# TopLevel.net
KiCad netlist of a schematic drawn in Altium Designer
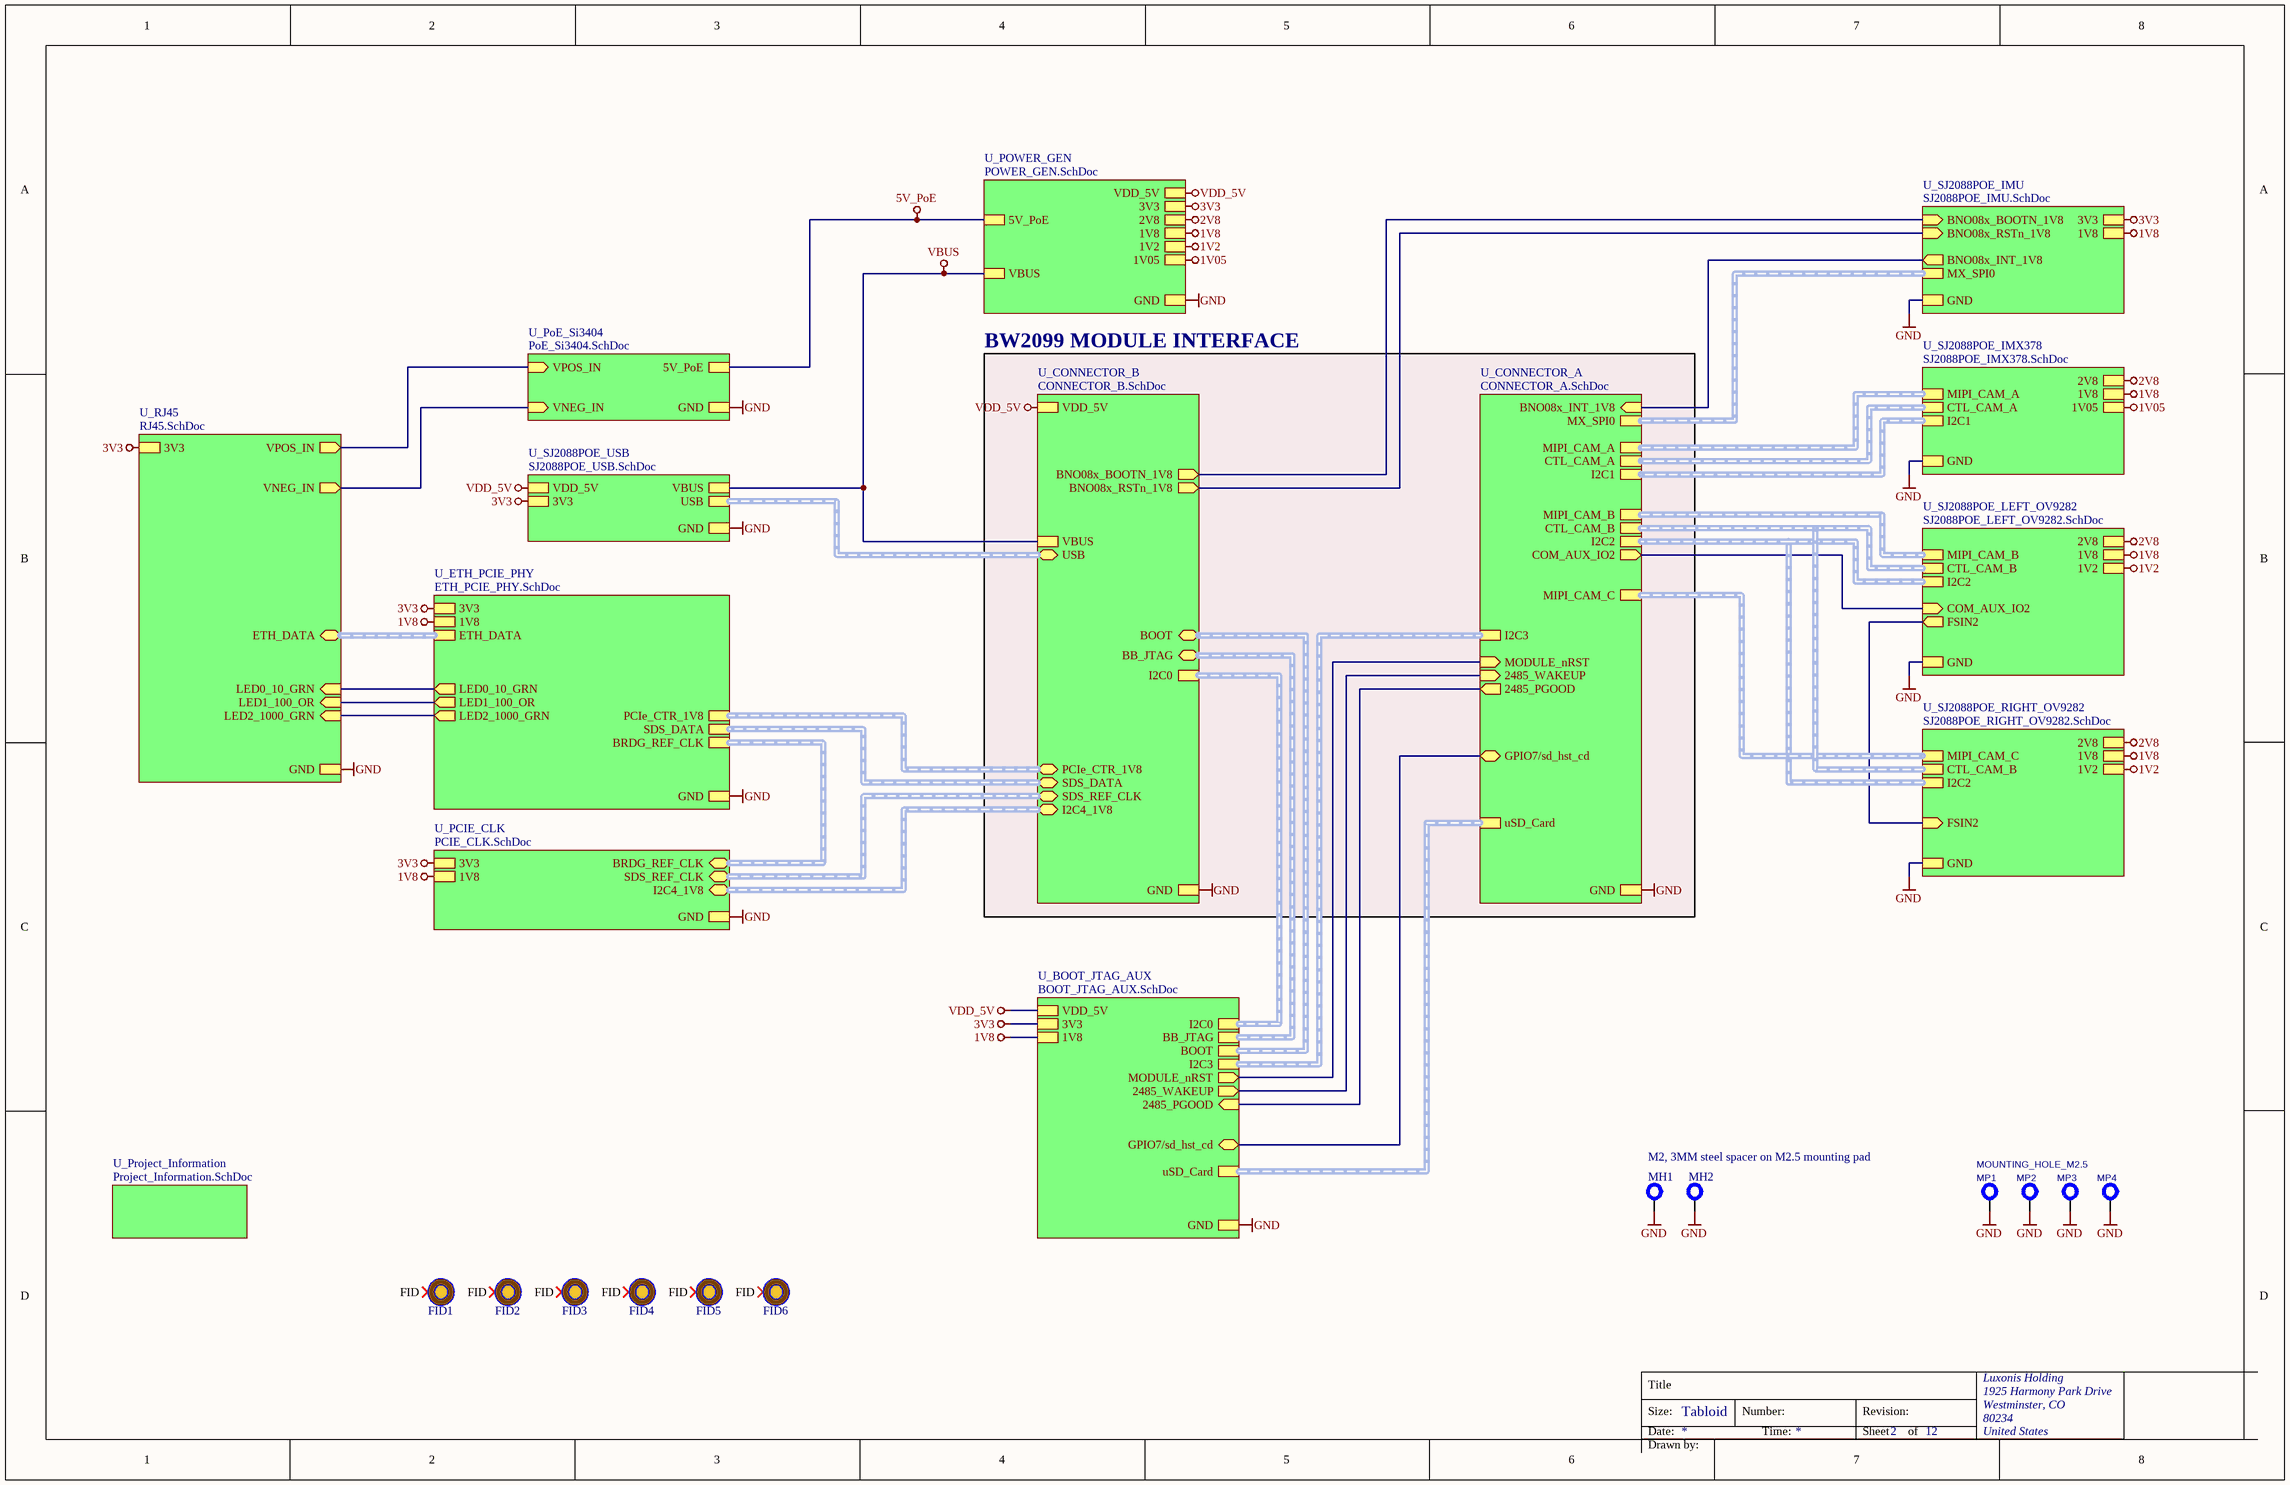
[diagram p0: TopLevel.SchDoc]

(export (version "E")
  (design (tool "Eeschema 10.0.6"))
  (components
    (comp (ref "FID1")
      (value "FIDUCIAL_ROUND_1MM")
      (footprint "LuxonisMaster:FIDUCIAL_ROUND_1MM")
      (description "Fiducial with various available footprints")
      (libsource (lib "LuxonisMaster") (part "FIDUCIAL"))
    )
    (comp (ref "FID2")
      (value "FIDUCIAL_ROUND_1MM")
      (footprint "LuxonisMaster:FIDUCIAL_ROUND_1MM")
      (description "Fiducial with various available footprints")
      (libsource (lib "LuxonisMaster") (part "FIDUCIAL"))
    )
    (comp (ref "FID3")
      (value "FIDUCIAL_ROUND_1MM")
      (footprint "LuxonisMaster:FIDUCIAL_ROUND_1MM")
      (description "Fiducial with various available footprints")
      (libsource (lib "LuxonisMaster") (part "FIDUCIAL"))
    )
    (comp (ref "FID4")
      (value "FIDUCIAL_ROUND_1MM")
      (footprint "LuxonisMaster:FIDUCIAL_ROUND_1MM")
      (description "Fiducial with various available footprints")
      (libsource (lib "LuxonisMaster") (part "FIDUCIAL"))
    )
    (comp (ref "FID5")
      (value "FIDUCIAL_ROUND_1MM")
      (footprint "LuxonisMaster:FIDUCIAL_ROUND_1MM")
      (description "Fiducial with various available footprints")
      (libsource (lib "LuxonisMaster") (part "FIDUCIAL"))
    )
    (comp (ref "FID6")
      (value "FIDUCIAL_ROUND_1MM")
      (footprint "LuxonisMaster:FIDUCIAL_ROUND_1MM")
      (description "Fiducial with various available footprints")
      (libsource (lib "LuxonisMaster") (part "FIDUCIAL"))
    )
    (comp (ref "MH1")
      (value "M2, 3MM steel spacer on M2.5 mounting pad")
      (footprint "LuxonisMaster:9774030243R")
      (description "MP ROUND STANDOFF M2X0.4 STEEL 3MM")
      (libsource (lib "LuxonisMaster") (part "9774030243R"))
    )
    (comp (ref "MH2")
      (value "M2, 3MM steel spacer on M2.5 mounting pad")
      (footprint "LuxonisMaster:9774030243R")
      (description "MP ROUND STANDOFF M2X0.4 STEEL 3MM")
      (libsource (lib "LuxonisMaster") (part "9774030243R"))
    )
    (comp (ref "MP1")
      (value "MOUNTING_HOLE_M2.5")
      (footprint "LuxonisMaster:MOUNTING_HOLE_M2.5")
      (description "=CurrentFootprint")
      (libsource (lib "LuxonisMaster") (part "MP_Mounting-Holes"))
    )
    (comp (ref "MP2")
      (value "MOUNTING_HOLE_M2.5")
      (footprint "LuxonisMaster:MOUNTING_HOLE_M2.5")
      (description "=CurrentFootprint")
      (libsource (lib "LuxonisMaster") (part "MP_Mounting-Holes"))
    )
    (comp (ref "MP3")
      (value "MOUNTING_HOLE_M2.5")
      (footprint "LuxonisMaster:MOUNTING_HOLE_M2.5")
      (description "=CurrentFootprint")
      (libsource (lib "LuxonisMaster") (part "MP_Mounting-Holes"))
    )
    (comp (ref "MP4")
      (value "MOUNTING_HOLE_M2.5")
      (footprint "LuxonisMaster:MOUNTING_HOLE_M2.5")
      (description "=CurrentFootprint")
      (libsource (lib "LuxonisMaster") (part "MP_Mounting-Holes"))
    )
  )
  (nets
    (net (code "41") (name "GND") (class "Default")
      (node (ref "MH1") (pin "1") (pintype "passive"))
      (node (ref "MH2") (pin "1") (pintype "passive"))
      (node (ref "MP1") (pin "1") (pintype "passive"))
      (node (ref "MP2") (pin "1") (pintype "passive"))
      (node (ref "MP3") (pin "1") (pintype "passive"))
      (node (ref "MP4") (pin "1") (pintype "passive"))
    )
    (net (code "44") (name "unconnected-(FID1-PadFID)") (class "Default")
      (node (ref "FID1") (pin "FID") (pinfunction "FID_FID") (pintype "input+no_connect"))
    )
    (net (code "45") (name "unconnected-(FID2-PadFID)") (class "Default")
      (node (ref "FID2") (pin "FID") (pinfunction "FID_FID") (pintype "input+no_connect"))
    )
    (net (code "46") (name "unconnected-(FID3-PadFID)") (class "Default")
      (node (ref "FID3") (pin "FID") (pinfunction "FID_FID") (pintype "input+no_connect"))
    )
    (net (code "47") (name "unconnected-(FID4-PadFID)") (class "Default")
      (node (ref "FID4") (pin "FID") (pinfunction "FID_FID") (pintype "input+no_connect"))
    )
    (net (code "48") (name "unconnected-(FID5-PadFID)") (class "Default")
      (node (ref "FID5") (pin "FID") (pinfunction "FID_FID") (pintype "input+no_connect"))
    )
    (net (code "49") (name "unconnected-(FID6-PadFID)") (class "Default")
      (node (ref "FID6") (pin "FID") (pinfunction "FID_FID") (pintype "input+no_connect"))
    )
  )
)
